# Switches.net
KiCad netlist of a schematic drawn in Altium Designer
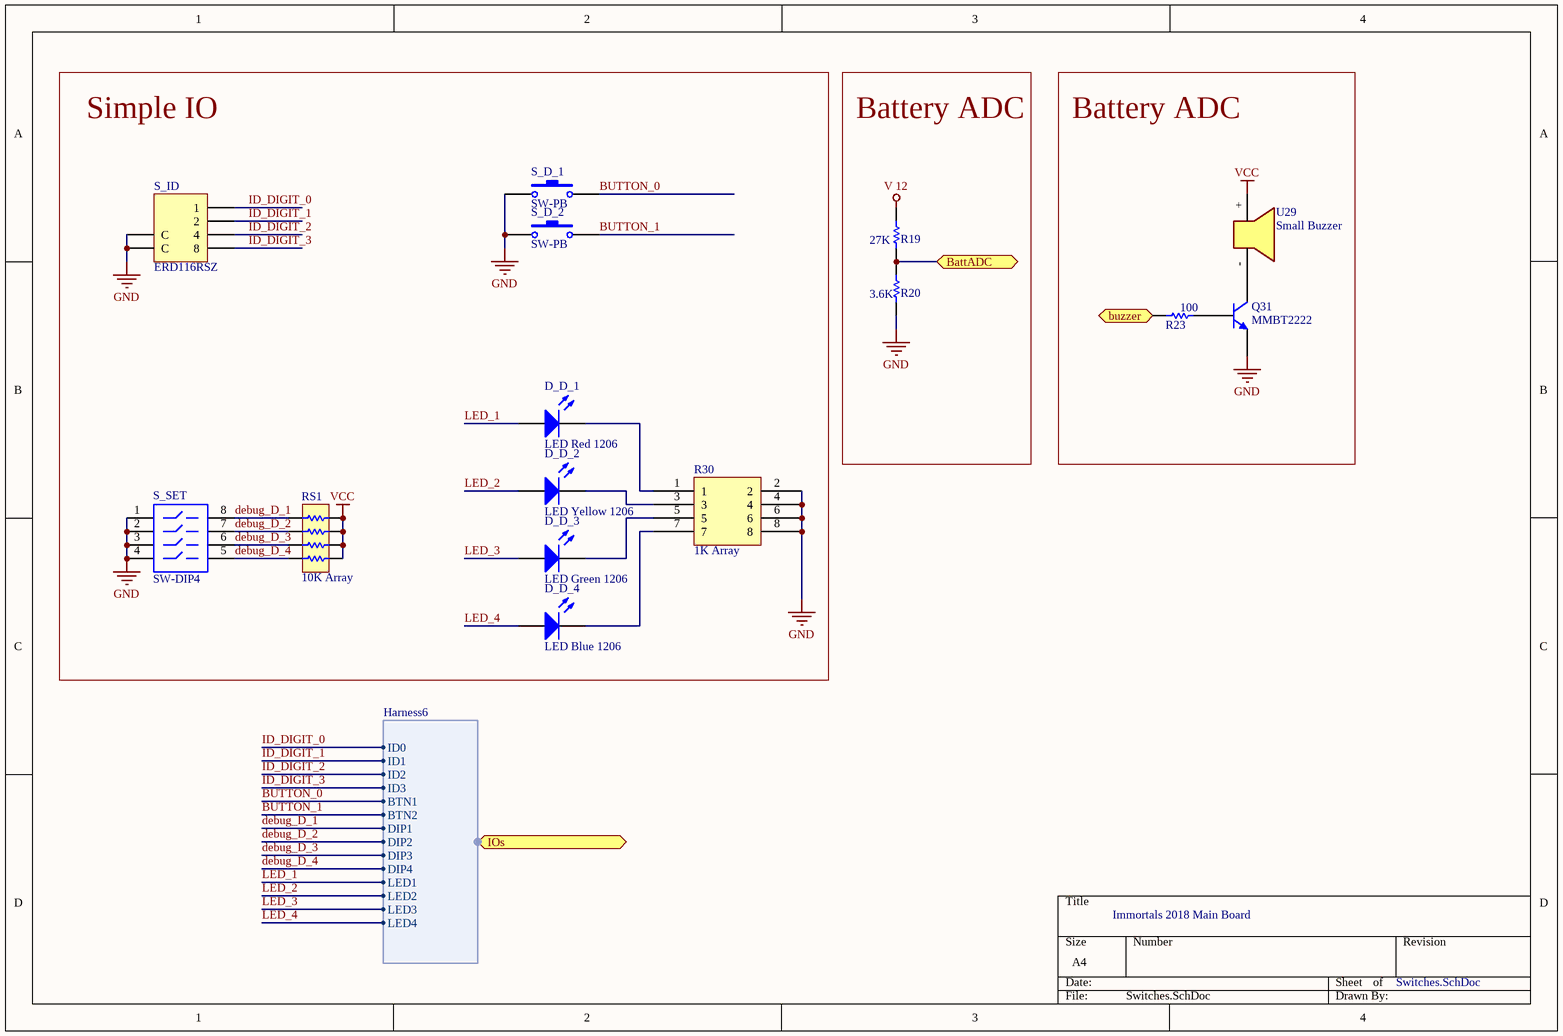
[diagram p0: Switches.SchDoc]

(export (version "E")
  (design (tool "Eeschema 10.0.6"))
  (components
    (comp (ref "D_D_1")
      (value "LED Red 1206")
      (footprint "REV(5):3.2X1.6X1.1 - RED")
      (description "Typical RED, GREEN, YELLOW, AMBER GaAs LED")
      (fields (field (name "PUBLISHER") "Altium Limited"))
      (libsource (lib "Miscellaneous Devices") (part "LED2"))
    )
    (comp (ref "D_D_2")
      (value "LED Yellow 1206")
      (footprint "3.2X1.6X1.1 - YELLOW")
      (description "Typical RED, GREEN, YELLOW, AMBER GaAs LED")
      (fields (field (name "PUBLISHER") "Altium Limited"))
      (libsource (lib "Miscellaneous Devices") (part "LED2"))
    )
    (comp (ref "D_D_3")
      (value "LED Green 1206")
      (footprint "REV(5):3.2X1.6X1.1 - GREEN")
      (description "Typical RED, GREEN, YELLOW, AMBER GaAs LED")
      (fields (field (name "PUBLISHER") "Altium Limited"))
      (libsource (lib "Miscellaneous Devices") (part "LED2"))
    )
    (comp (ref "D_D_4")
      (value "LED Blue 1206")
      (footprint "3.2X1.6X1.1 - BLUE")
      (description "Typical RED, GREEN, YELLOW, AMBER GaAs LED")
      (fields (field (name "PUBLISHER") "Altium Limited"))
      (libsource (lib "Miscellaneous Devices") (part "LED2"))
    )
    (comp (ref "Q31")
      (value "MMBT2222")
      (footprint "SOT23")
      (description "Transistor NPN Silicon,SMD")
      (fields (field (name "PUBLISHER") "Altium Limited"))
      (libsource (lib "SamatecLib") (part "MMBT2222ALT1"))
    )
    (comp (ref "R19")
      (value "27K")
      (footprint "R0603")
      (description "Res 0603")
      (fields (field (name "Comment") "Res 27K 0603"))
      (libsource (lib "SamatecLib") (part "R0603"))
    )
    (comp (ref "R20")
      (value "3.6K")
      (footprint "R0603")
      (description "Res 0603")
      (fields (field (name "Comment") "Res 3.6K 0603"))
      (libsource (lib "SamatecLib") (part "R0603"))
    )
    (comp (ref "R23")
      (value "100")
      (footprint "R0603")
      (description "Res 0603")
      (fields (field (name "Comment") "Res 100 0603"))
      (libsource (lib "SamatecLib") (part "R0603"))
    )
    (comp (ref "R30")
      (value "1K Array")
      (footprint "RES-0603x4")
      (description "Array resistors")
      (libsource (lib "REV(5)") (part "RES 0603x4"))
    )
    (comp (ref "RS1")
      (value "10K Array")
      (footprint "RES-4B")
      (description "Resistor Array ,SMD")
      (libsource (lib "SamatecLib") (part "Resister Array"))
    )
    (comp (ref "S_D_1")
      (value "SW-PB")
      (footprint "SPST-2")
      (description "Switch")
      (fields (field (name "PUBLISHER") "Altium Limited"))
      (libsource (lib "REV(5)") (part "SW-PB"))
    )
    (comp (ref "S_D_2")
      (value "SW-PB")
      (footprint "SPST-2")
      (description "Switch")
      (fields (field (name "PUBLISHER") "Altium Limited"))
      (libsource (lib "REV(5)") (part "SW-PB"))
    )
    (comp (ref "S_ID")
      (value "ERD116RSZ")
      (footprint "ERD116RSZ")
      (description "Rotary Switch")
      (libsource (lib "REV(5)") (part "Rotary Switch"))
    )
    (comp (ref "S_SET")
      (value "SW-DIP4")
      (footprint "DIP-8-SW")
      (description "DIP Switch")
      (fields (field (name "PUBLISHER") "Altium Limited"))
      (libsource (lib "REV(5)") (part "SW-DIP4"))
    )
    (comp (ref "U29")
      (value "Small Buzzer")
      (footprint "my_BUZZER")
      (libsource (lib "REV(5)") (part "my_Buzzer"))
    )
  )
  (nets
    (net (code "2") (name "/BUTTON_0") (class "Default")
      (node (ref "S_D_1") (pin "2") (pinfunction "2_2") (pintype "passive"))
    )
    (net (code "3") (name "/BUTTON_1") (class "Default")
      (node (ref "S_D_2") (pin "2") (pinfunction "2_2") (pintype "passive"))
    )
    (net (code "4") (name "/BattADC") (class "Default")
      (node (ref "R19") (pin "1") (pinfunction "1_1") (pintype "passive"))
      (node (ref "R20") (pin "2") (pinfunction "2_2") (pintype "passive"))
    )
    (net (code "5") (name "/ID_DIGIT_0") (class "Default")
      (node (ref "S_ID") (pin "1") (pinfunction "1_1") (pintype "passive"))
    )
    (net (code "6") (name "/ID_DIGIT_1") (class "Default")
      (node (ref "S_ID") (pin "4") (pinfunction "2_4") (pintype "passive"))
    )
    (net (code "7") (name "/ID_DIGIT_2") (class "Default")
      (node (ref "S_ID") (pin "3") (pinfunction "4_3") (pintype "passive"))
    )
    (net (code "8") (name "/ID_DIGIT_3") (class "Default")
      (node (ref "S_ID") (pin "6") (pinfunction "8_6") (pintype "passive"))
    )
    (net (code "9") (name "/LED_1") (class "Default")
      (node (ref "D_D_1") (pin "1") (pinfunction "A_1") (pintype "passive"))
    )
    (net (code "10") (name "/LED_2") (class "Default")
      (node (ref "D_D_2") (pin "1") (pinfunction "A_1") (pintype "passive"))
    )
    (net (code "11") (name "/LED_3") (class "Default")
      (node (ref "D_D_3") (pin "1") (pinfunction "A_1") (pintype "passive"))
    )
    (net (code "12") (name "/LED_4") (class "Default")
      (node (ref "D_D_4") (pin "1") (pinfunction "A_1") (pintype "passive"))
    )
    (net (code "13") (name "/buzzer") (class "Default")
      (node (ref "R23") (pin "2") (pinfunction "2_2") (pintype "passive"))
    )
    (net (code "14") (name "/debug_D_1") (class "Default")
      (node (ref "RS1") (pin "8") (pinfunction "8_8") (pintype "passive"))
      (node (ref "S_SET") (pin "8") (pinfunction "8_8") (pintype "passive"))
    )
    (net (code "15") (name "/debug_D_2") (class "Default")
      (node (ref "RS1") (pin "6") (pinfunction "6_6") (pintype "passive"))
      (node (ref "S_SET") (pin "7") (pinfunction "7_7") (pintype "passive"))
    )
    (net (code "16") (name "/debug_D_3") (class "Default")
      (node (ref "RS1") (pin "4") (pinfunction "4_4") (pintype "passive"))
      (node (ref "S_SET") (pin "6") (pinfunction "6_6") (pintype "passive"))
    )
    (net (code "17") (name "/debug_D_4") (class "Default")
      (node (ref "RS1") (pin "2") (pinfunction "2_2") (pintype "passive"))
      (node (ref "S_SET") (pin "5") (pinfunction "5_5") (pintype "passive"))
    )
    (net (code "19") (name "GND") (class "Default")
      (node (ref "Q31") (pin "2") (pinfunction "E_2") (pintype "passive"))
      (node (ref "R20") (pin "1") (pinfunction "1_1") (pintype "passive"))
      (node (ref "R30") (pin "2") (pinfunction "2_2") (pintype "passive"))
      (node (ref "R30") (pin "4") (pinfunction "4_4") (pintype "passive"))
      (node (ref "R30") (pin "6") (pinfunction "6_6") (pintype "passive"))
      (node (ref "R30") (pin "8") (pinfunction "8_8") (pintype "passive"))
      (node (ref "S_D_1") (pin "1") (pinfunction "1_1") (pintype "passive"))
      (node (ref "S_D_2") (pin "1") (pinfunction "1_1") (pintype "passive"))
      (node (ref "S_ID") (pin "2") (pinfunction "C_2") (pintype "passive"))
      (node (ref "S_ID") (pin "5") (pinfunction "C_5") (pintype "passive"))
      (node (ref "S_SET") (pin "1") (pinfunction "1_1") (pintype "passive"))
      (node (ref "S_SET") (pin "2") (pinfunction "2_2") (pintype "passive"))
      (node (ref "S_SET") (pin "3") (pinfunction "3_3") (pintype "passive"))
      (node (ref "S_SET") (pin "4") (pinfunction "4_4") (pintype "passive"))
    )
    (net (code "20") (name "Net-(D_D_1-K)") (class "Default")
      (node (ref "D_D_1") (pin "2") (pinfunction "K_2") (pintype "passive"))
      (node (ref "R30") (pin "1") (pinfunction "1_1") (pintype "passive"))
    )
    (net (code "21") (name "Net-(D_D_2-K)") (class "Default")
      (node (ref "D_D_2") (pin "2") (pinfunction "K_2") (pintype "passive"))
      (node (ref "R30") (pin "3") (pinfunction "3_3") (pintype "passive"))
    )
    (net (code "22") (name "Net-(D_D_3-K)") (class "Default")
      (node (ref "D_D_3") (pin "2") (pinfunction "K_2") (pintype "passive"))
      (node (ref "R30") (pin "5") (pinfunction "5_5") (pintype "passive"))
    )
    (net (code "23") (name "Net-(D_D_4-K)") (class "Default")
      (node (ref "D_D_4") (pin "2") (pinfunction "K_2") (pintype "passive"))
      (node (ref "R30") (pin "7") (pinfunction "7_7") (pintype "passive"))
    )
    (net (code "24") (name "Net-(Q31-B)") (class "Default")
      (node (ref "Q31") (pin "1") (pinfunction "B_1") (pintype "passive"))
      (node (ref "R23") (pin "1") (pinfunction "1_1") (pintype "passive"))
    )
    (net (code "25") (name "Net-(Q31-C)") (class "Default")
      (node (ref "Q31") (pin "3") (pinfunction "C_3") (pintype "passive"))
      (node (ref "U29") (pin "-") (pinfunction "2_-") (pintype "power_in"))
    )
    (net (code "26") (name "V 12") (class "Default")
      (node (ref "R19") (pin "2") (pinfunction "2_2") (pintype "passive"))
    )
    (net (code "27") (name "VCC") (class "Default")
      (node (ref "RS1") (pin "1") (pinfunction "1_1") (pintype "passive"))
      (node (ref "RS1") (pin "3") (pinfunction "3_3") (pintype "passive"))
      (node (ref "RS1") (pin "5") (pinfunction "5_5") (pintype "passive"))
      (node (ref "RS1") (pin "7") (pinfunction "7_7") (pintype "passive"))
      (node (ref "U29") (pin "+") (pinfunction "1_+") (pintype "power_in"))
    )
  )
)
